# powerInput.net
KiCad netlist of a schematic drawn in EAGLE
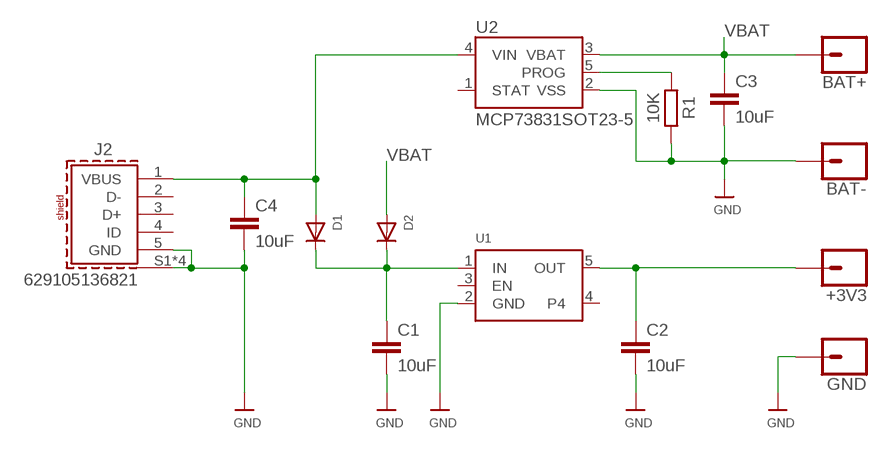
[diagram p0: schematic, sheet 1]

(export (version "E")
  (design (tool "Eeschema 10.0.6"))
  (components
    (comp (ref "+3V3")
      (value "CONN_01")
      (footprint "eagle-import:1X01")
      (libsource (lib "eagle-import") (part "CONN_01"))
    )
    (comp (ref "BAT+")
      (value "CONN_01")
      (footprint "eagle-import:1X01")
      (libsource (lib "eagle-import") (part "CONN_01"))
    )
    (comp (ref "BAT-")
      (value "CONN_01")
      (footprint "eagle-import:1X01")
      (libsource (lib "eagle-import") (part "CONN_01"))
    )
    (comp (ref "C1")
      (value "10uF")
      (footprint "eagle-import:0603")
      (libsource (lib "eagle-import") (part "10UF-0603-6.3V-20%"))
    )
    (comp (ref "C2")
      (value "10uF")
      (footprint "eagle-import:0603")
      (libsource (lib "eagle-import") (part "10UF-0603-6.3V-20%"))
    )
    (comp (ref "C3")
      (value "10uF")
      (footprint "eagle-import:0603")
      (libsource (lib "eagle-import") (part "10UF-0603-6.3V-20%"))
    )
    (comp (ref "C4")
      (value "10uF")
      (footprint "eagle-import:0603")
      (libsource (lib "eagle-import") (part "10UF-0603-6.3V-20%"))
    )
    (comp (ref "D1")
      (value "DIODESOD-123")
      (footprint "eagle-import:SOD-123")
      (libsource (lib "eagle-import") (part "DIODESOD-123"))
    )
    (comp (ref "D2")
      (value "DIODESOD-123")
      (footprint "eagle-import:SOD-123")
      (libsource (lib "eagle-import") (part "DIODESOD-123"))
    )
    (comp (ref "GND")
      (value "CONN_01")
      (footprint "eagle-import:1X01")
      (libsource (lib "eagle-import") (part "CONN_01"))
    )
    (comp (ref "J2")
      (value "629105136821")
      (footprint "eagle-import:629105136821")
      (libsource (lib "eagle-import") (part "629105136821"))
    )
    (comp (ref "R1")
      (value "10K")
      (footprint "eagle-import:RESC1608X60")
      (libsource (lib "eagle-import") (part "RCHIP-0603(1608-METRIC)_"))
    )
    (comp (ref "U1")
      (value "VREG_SOT23-5")
      (footprint "eagle-import:SOT23-5_1")
      (libsource (lib "eagle-import") (part "VREG_SOT23-5"))
    )
    (comp (ref "U2")
      (value "MCP73831SOT23-5")
      (footprint "eagle-import:SOT95P280X110-5")
      (libsource (lib "eagle-import") (part "MCP73831SOT23-5"))
    )
  )
  (nets
    (net (code "1") (name "/VBAT") (class "Default")
      (node (ref "BAT+") (pin "1") (pinfunction "1_1") (pintype "passive"))
      (node (ref "C3") (pin "1") (pinfunction "1_1") (pintype "passive"))
      (node (ref "D2") (pin "A") (pinfunction "A_A") (pintype "passive"))
      (node (ref "U2") (pin "3") (pinfunction "VBAT_3") (pintype "power_in"))
    )
    (net (code "2") (name "GND") (class "Default")
      (node (ref "BAT-") (pin "1") (pinfunction "1_1") (pintype "passive"))
      (node (ref "C1") (pin "2") (pinfunction "2_2") (pintype "passive"))
      (node (ref "C2") (pin "2") (pinfunction "2_2") (pintype "passive"))
      (node (ref "C3") (pin "2") (pinfunction "2_2") (pintype "passive"))
      (node (ref "C4") (pin "2") (pinfunction "2_2") (pintype "passive"))
      (node (ref "GND") (pin "1") (pinfunction "1_1") (pintype "passive"))
      (node (ref "J2") (pin "5") (pinfunction "GND_5") (pintype "passive"))
      (node (ref "J2") (pin "S1") (pinfunction "SHIELD_S1") (pintype "passive"))
      (node (ref "J2") (pin "S2") (pinfunction "SHIELD_S2") (pintype "passive"))
      (node (ref "J2") (pin "S3") (pinfunction "SHIELD_S3") (pintype "passive"))
      (node (ref "J2") (pin "S4") (pinfunction "SHIELD_S4") (pintype "passive"))
      (node (ref "R1") (pin "2") (pinfunction "2_2") (pintype "passive"))
      (node (ref "U1") (pin "2") (pinfunction "GND_2") (pintype "power_in"))
      (node (ref "U2") (pin "2") (pinfunction "VSS_2") (pintype "power_in"))
    )
    (net (code "3") (name "Net-(J2-VBUS)") (class "Default")
      (node (ref "C4") (pin "1") (pinfunction "1_1") (pintype "passive"))
      (node (ref "D1") (pin "A") (pinfunction "A_A") (pintype "passive"))
      (node (ref "J2") (pin "1") (pinfunction "VBUS_1") (pintype "passive"))
      (node (ref "U2") (pin "4") (pinfunction "VIN_4") (pintype "power_in"))
    )
    (net (code "4") (name "Net-(U1-IN)") (class "Default")
      (node (ref "C1") (pin "1") (pinfunction "1_1") (pintype "passive"))
      (node (ref "D1") (pin "C") (pinfunction "C_C") (pintype "passive"))
      (node (ref "D2") (pin "C") (pinfunction "C_C") (pintype "passive"))
      (node (ref "U1") (pin "1") (pinfunction "IN_1") (pintype "power_in"))
    )
    (net (code "5") (name "Net-(U1-OUT)") (class "Default")
      (node (ref "+3V3") (pin "1") (pinfunction "1_1") (pintype "passive"))
      (node (ref "C2") (pin "1") (pinfunction "1_1") (pintype "passive"))
      (node (ref "U1") (pin "5") (pinfunction "OUT_5") (pintype "power_in"))
    )
    (net (code "6") (name "Net-(U2-PROG)") (class "Default")
      (node (ref "R1") (pin "1") (pinfunction "1_1") (pintype "passive"))
      (node (ref "U2") (pin "5") (pinfunction "PROG_5") (pintype "input"))
    )
    (net (code "7") (name "unconnected-(J2-D+-Pad3)") (class "Default")
      (node (ref "J2") (pin "3") (pinfunction "D+_3") (pintype "passive"))
    )
    (net (code "8") (name "unconnected-(J2-D--Pad2)") (class "Default")
      (node (ref "J2") (pin "2") (pinfunction "D-_2") (pintype "passive"))
    )
    (net (code "9") (name "unconnected-(J2-ID-Pad4)") (class "Default")
      (node (ref "J2") (pin "4") (pinfunction "ID_4") (pintype "passive"))
    )
    (net (code "10") (name "unconnected-(U1-EN-Pad3)") (class "Default")
      (node (ref "U1") (pin "3") (pinfunction "EN_3") (pintype "input"))
    )
    (net (code "11") (name "unconnected-(U1-P4-Pad4)") (class "Default")
      (node (ref "U1") (pin "4") (pinfunction "P4_4") (pintype "bidirectional"))
    )
    (net (code "12") (name "unconnected-(U2-STAT-Pad1)") (class "Default")
      (node (ref "U2") (pin "1") (pinfunction "STAT_1") (pintype "output"))
    )
  )
)
